# cape-eeprom.net
KiCad netlist of a schematic drawn in EAGLE
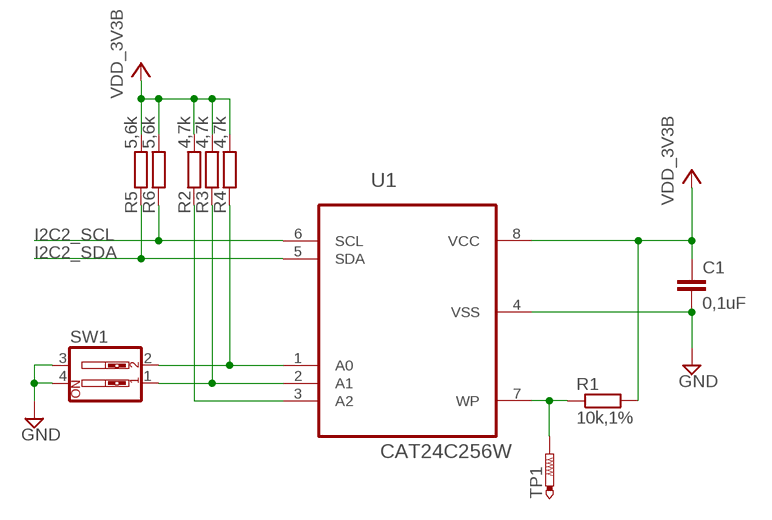
[diagram p0: schematic, sheet 1]

(export (version "E")
  (design (tool "Eeschema 10.0.6"))
  (components
    (comp (ref "C1")
      (value "0,1uF")
      (footprint "eagle-import:C2.5-3")
      (libsource (lib "eagle-import") (part "C2,5-3"))
    )
    (comp (ref "R1")
      (value "10k,1%")
      (footprint "eagle-import:M0805")
      (libsource (lib "eagle-import") (part "resistor_R-EU_M0805"))
    )
    (comp (ref "R2")
      (value "4,7k")
      (footprint "eagle-import:M1206")
      (libsource (lib "eagle-import") (part "R-EU_M1206"))
    )
    (comp (ref "R3")
      (value "4,7k")
      (footprint "eagle-import:M1206")
      (libsource (lib "eagle-import") (part "R-EU_M1206"))
    )
    (comp (ref "R4")
      (value "4,7k")
      (footprint "eagle-import:M1206")
      (libsource (lib "eagle-import") (part "R-EU_M1206"))
    )
    (comp (ref "R5")
      (value "5,6k")
      (footprint "eagle-import:M1206")
      (libsource (lib "eagle-import") (part "R-EU_M1206"))
    )
    (comp (ref "R6")
      (value "5,6k")
      (footprint "eagle-import:M1206")
      (libsource (lib "eagle-import") (part "R-EU_M1206"))
    )
    (comp (ref "SW1")
      (value "SW_DIP-2")
      (footprint "eagle-import:EDG-02")
      (libsource (lib "eagle-import") (part "SW_DIP-2"))
    )
    (comp (ref "TP1")
      (value "PTR1B1,27")
      (footprint "eagle-import:B1,27")
      (libsource (lib "eagle-import") (part "PTR1B1,27"))
    )
    (comp (ref "U1")
      (value "CAT24C256W")
      (footprint "eagle-import:SOIC127P600X175-8N")
      (fields (field (name "MPN") "CAT24C256WI-G"))
      (libsource (lib "eagle-import") (part "CAT24C256W"))
    )
  )
  (nets
    (net (code "1") (name "/I2C2_SCL") (class "Default")
      (node (ref "R6") (pin "1") (pinfunction "1_1") (pintype "passive"))
      (node (ref "U1") (pin "6") (pinfunction "SCL_6") (pintype "input"))
    )
    (net (code "2") (name "/I2C2_SDA") (class "Default")
      (node (ref "R5") (pin "1") (pinfunction "1_1") (pintype "passive"))
      (node (ref "U1") (pin "5") (pinfunction "SDA_5") (pintype "bidirectional"))
    )
    (net (code "3") (name "GND") (class "Default")
      (node (ref "C1") (pin "2") (pinfunction "2_2") (pintype "passive"))
      (node (ref "SW1") (pin "3") (pinfunction "3_3") (pintype "passive"))
      (node (ref "SW1") (pin "4") (pinfunction "4_4") (pintype "passive"))
      (node (ref "U1") (pin "4") (pinfunction "VSS_4") (pintype "passive"))
    )
    (net (code "4") (name "Net-(U1-A0)") (class "Default")
      (node (ref "R4") (pin "1") (pinfunction "1_1") (pintype "passive"))
      (node (ref "SW1") (pin "2") (pinfunction "2_2") (pintype "passive"))
      (node (ref "U1") (pin "1") (pinfunction "A0_1") (pintype "input"))
    )
    (net (code "5") (name "Net-(U1-A1)") (class "Default")
      (node (ref "R3") (pin "1") (pinfunction "1_1") (pintype "passive"))
      (node (ref "SW1") (pin "1") (pinfunction "1_1") (pintype "passive"))
      (node (ref "U1") (pin "2") (pinfunction "A1_2") (pintype "input"))
    )
    (net (code "6") (name "Net-(U1-A2)") (class "Default")
      (node (ref "R2") (pin "1") (pinfunction "1_1") (pintype "passive"))
      (node (ref "U1") (pin "3") (pinfunction "A2_3") (pintype "input"))
    )
    (net (code "7") (name "Net-(U1-WP)") (class "Default")
      (node (ref "R1") (pin "1") (pinfunction "1_1") (pintype "passive"))
      (node (ref "TP1") (pin "TP") (pinfunction "TP_TP") (pintype "input"))
      (node (ref "U1") (pin "7") (pinfunction "WP_7") (pintype "input"))
    )
    (net (code "8") (name "VDD_3V3B") (class "Default")
      (node (ref "C1") (pin "1") (pinfunction "1_1") (pintype "passive"))
      (node (ref "R1") (pin "2") (pinfunction "2_2") (pintype "passive"))
      (node (ref "R2") (pin "2") (pinfunction "2_2") (pintype "passive"))
      (node (ref "R3") (pin "2") (pinfunction "2_2") (pintype "passive"))
      (node (ref "R4") (pin "2") (pinfunction "2_2") (pintype "passive"))
      (node (ref "R5") (pin "2") (pinfunction "2_2") (pintype "passive"))
      (node (ref "R6") (pin "2") (pinfunction "2_2") (pintype "passive"))
      (node (ref "U1") (pin "8") (pinfunction "VCC_8") (pintype "power_in"))
    )
  )
)
